# 12_TO_3V3_VOLTAGE_DIVIDER.net
KiCad netlist of a schematic drawn in Altium Designer
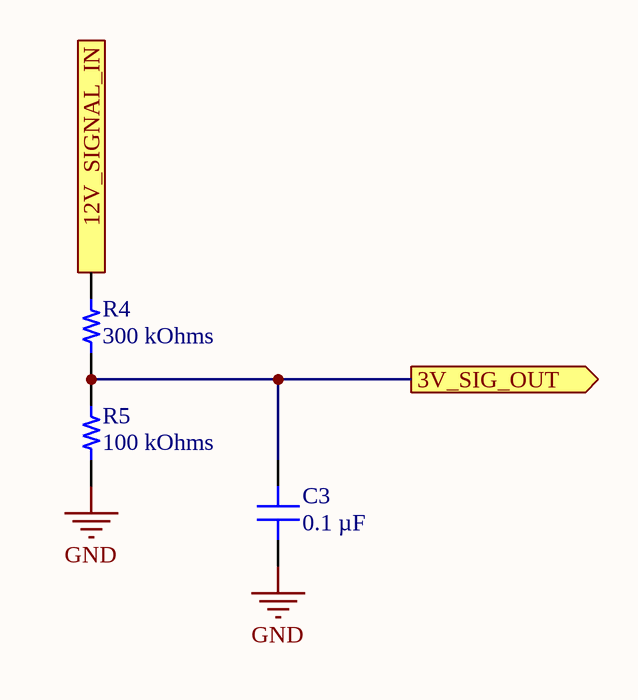
[diagram p0: 12_TO_3V3_VOLTAGE_DIVIDER.SchDoc]

(export (version "E")
  (design (tool "Eeschema 10.0.6"))
  (components
    (comp (ref "C3")
      (value "0.1 µF")
      (footprint "CAP 0805_2012")
      (description "CAP CER 0.1UF 50V X7R 0805")
      (fields (field (name "PART NUMBER") "CC0805MRX7R9BB104") (field (name "MANUFACTURER") "Yageo"))
      (libsource (lib "Celestial Altium Library - altium_library") (part "Capacitor"))
    )
    (comp (ref "R4")
      (value "300 kOhms")
      (footprint "RES 0805_2012")
      (description "RES SMD 300K OHM 5% 1/8W 0805")
      (fields (field (name "PART NUMBER") "CRCW0805300KJNEA") (field (name "MANUFACTURER") "Vishay Dale"))
      (libsource (lib "Celestial Altium Library - altium_library") (part "Resistor"))
    )
    (comp (ref "R5")
      (value "100 kOhms")
      (footprint "RES 0805_2012")
      (description "RES SMD 100K OHM 0.1% 1/10W 0805")
      (fields
        (field (name "PART NUMBER") "CPF0805B100KE")
        (field (name "MANUFACTURER") "TE Connectivity Passive Product")
      )
      (libsource (lib "Celestial Altium Library - altium_library") (part "Resistor"))
    )
  )
  (nets
    (net (code "1") (name "/3V_SIG_OUT") (class "Default")
      (node (ref "C3") (pin "2") (pinfunction "2_2") (pintype "passive"))
      (node (ref "R4") (pin "1") (pinfunction "1_1") (pintype "passive"))
      (node (ref "R5") (pin "2") (pinfunction "2_2") (pintype "passive"))
    )
    (net (code "2") (name "/12V_SIGNAL_IN") (class "Default")
      (node (ref "R4") (pin "2") (pinfunction "2_2") (pintype "passive"))
    )
    (net (code "3") (name "GND") (class "Default")
      (node (ref "C3") (pin "1") (pinfunction "1_1") (pintype "passive"))
      (node (ref "R5") (pin "1") (pinfunction "1_1") (pintype "passive"))
    )
  )
)
